# IWatch_MB.net
KiCad netlist of a schematic drawn in Altium Designer
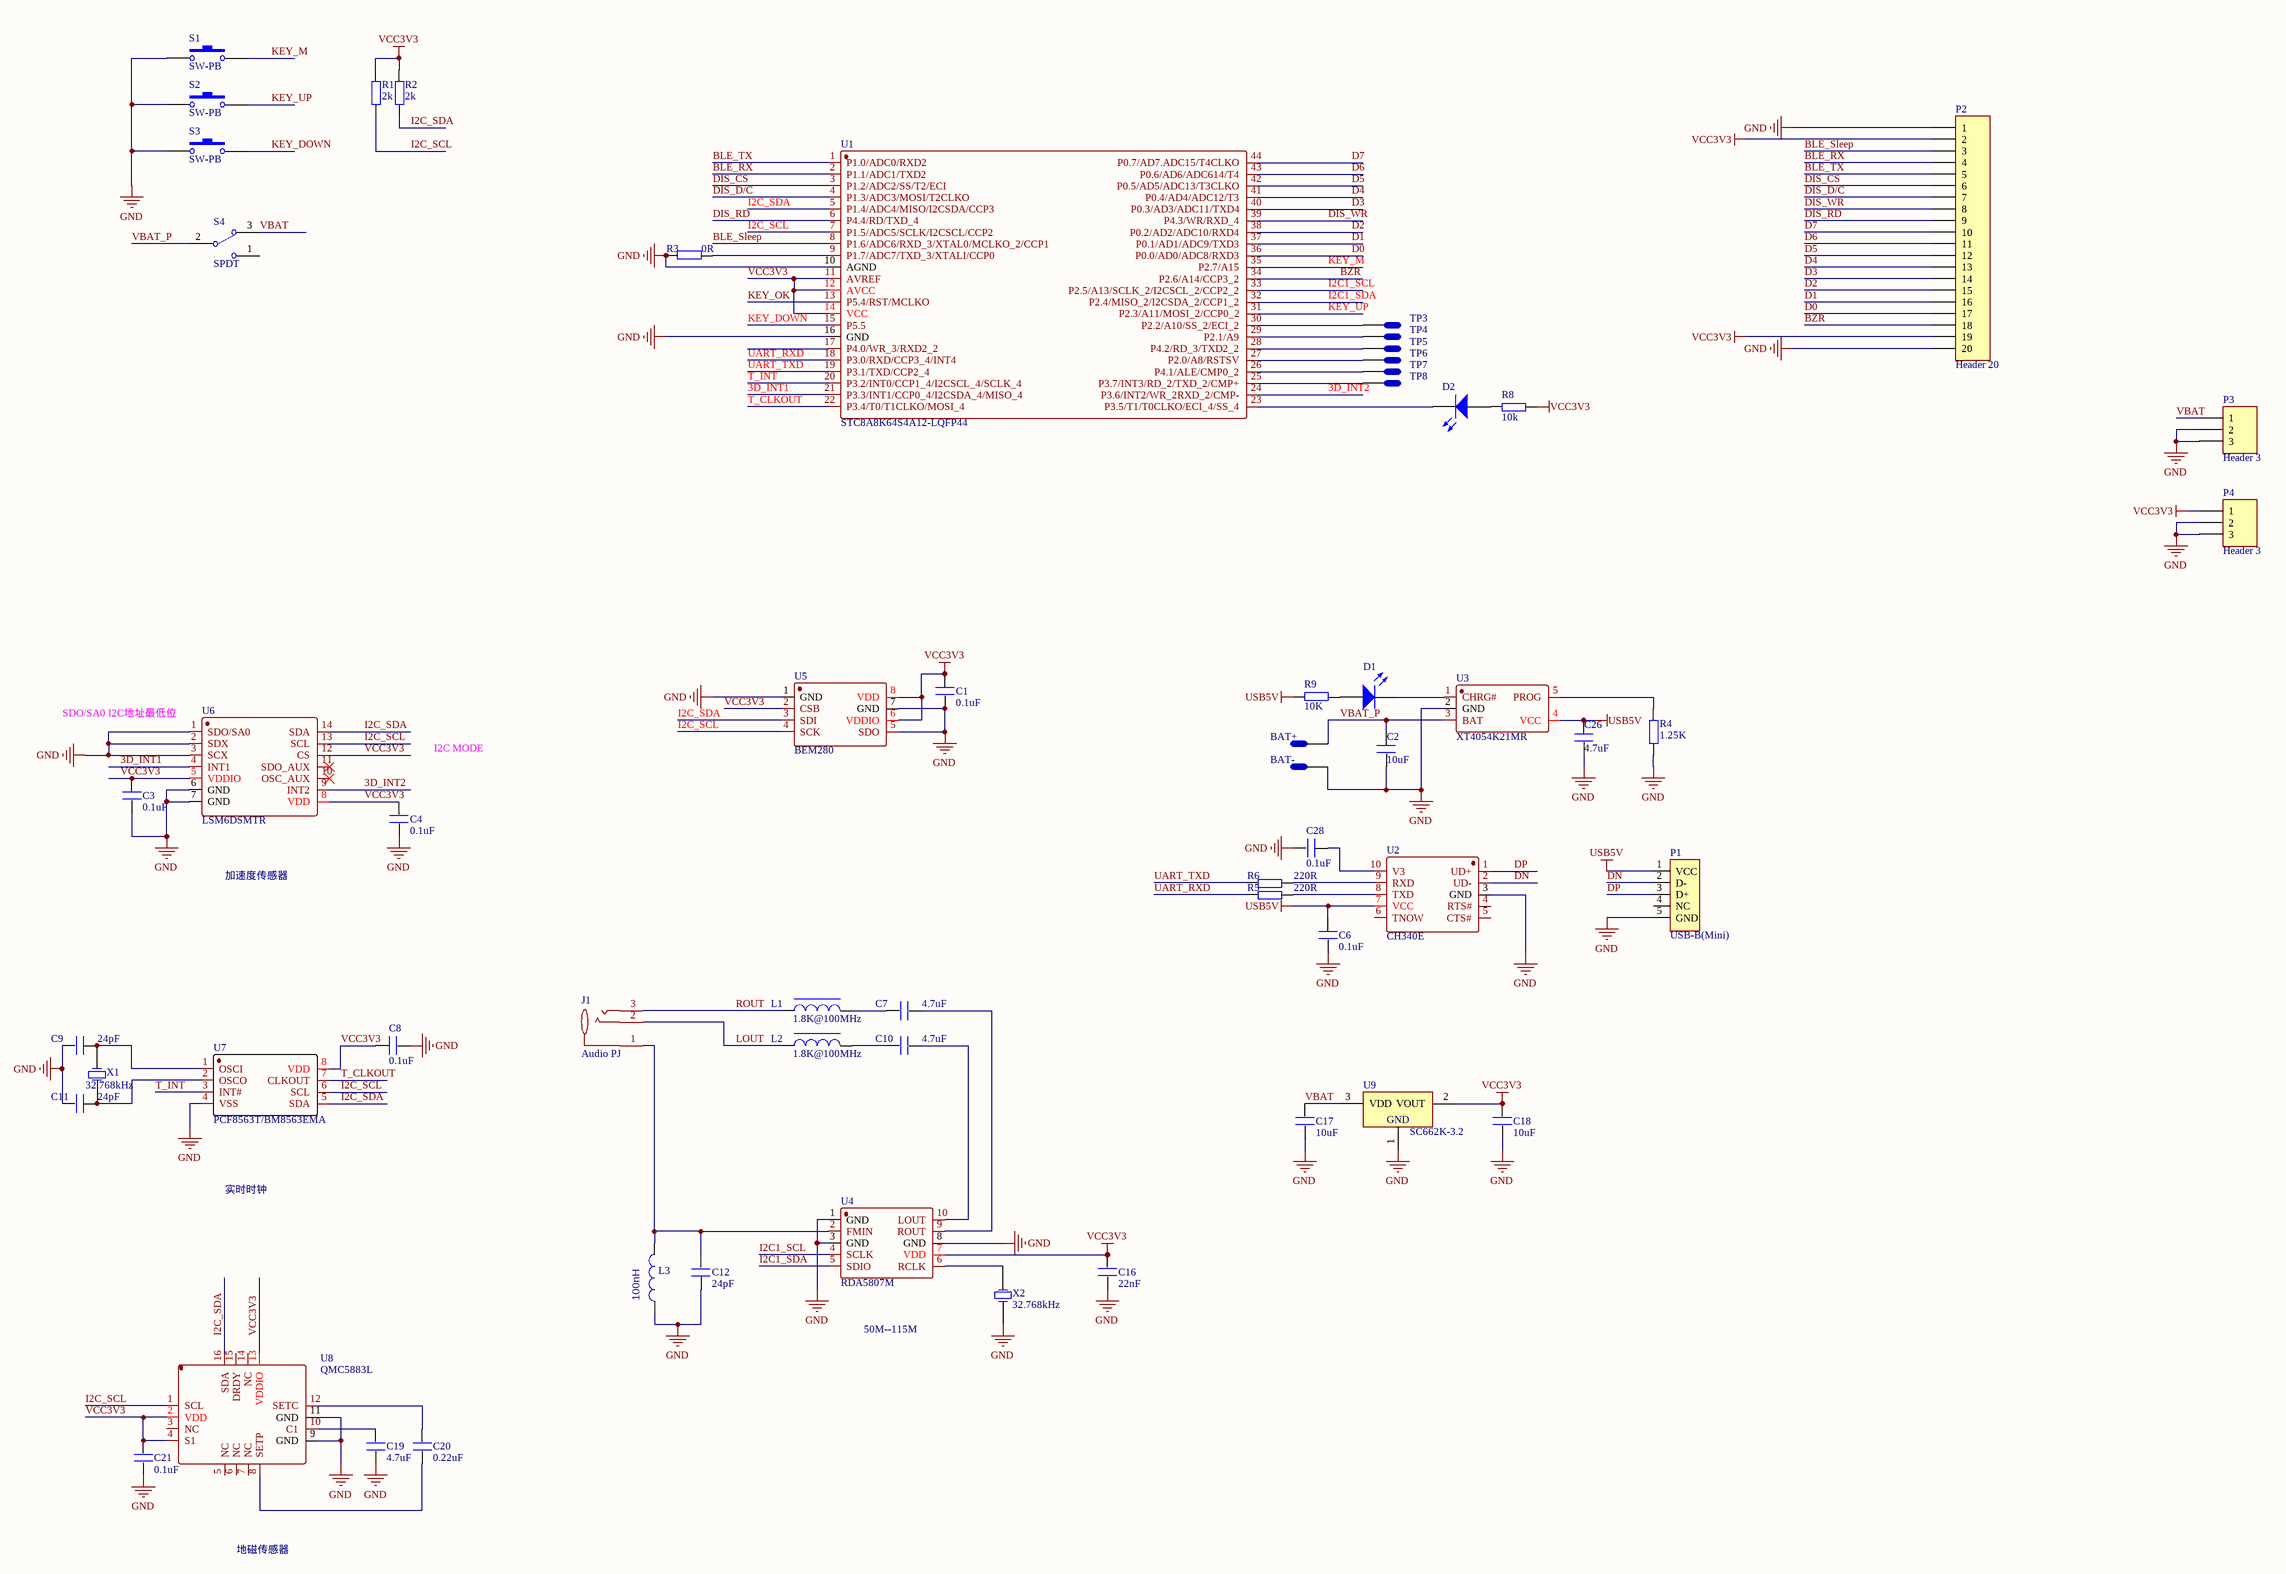
[diagram p0: IWatch_MB.SchDoc]

(export (version "E")
  (design (tool "Eeschema 10.0.6"))
  (components
    (comp (ref "BAT+")
      (value "TP")
      (footprint "TP_1mm")
      (description "TEST POINT")
      (libsource (lib "ADDI9033") (part "TP"))
    )
    (comp (ref "BAT-")
      (value "TP")
      (footprint "TP_1mm")
      (description "TEST POINT")
      (libsource (lib "ADDI9033") (part "TP"))
    )
    (comp (ref "C1")
      (value "0.1uF")
      (footprint "C0603")
      (libsource (lib "Explorer STM32F407封装库2") (part "C"))
    )
    (comp (ref "C2") (value "10uF") (footprint "C0603") (libsource (lib "Explorer STM32F407封装库2") (part "C")))
    (comp (ref "C3")
      (value "0.1uF")
      (footprint "C0603")
      (libsource (lib "Explorer STM32F407封装库2") (part "C"))
    )
    (comp (ref "C4")
      (value "0.1uF")
      (footprint "C0603")
      (libsource (lib "Explorer STM32F407封装库2") (part "C"))
    )
    (comp (ref "C6")
      (value "0.1uF")
      (footprint "C0603")
      (libsource (lib "Explorer STM32F407封装库2") (part "C"))
    )
    (comp (ref "C7")
      (value "4.7uF")
      (footprint "C0603")
      (libsource (lib "Explorer STM32F407封装库2") (part "C"))
    )
    (comp (ref "C8")
      (value "0.1uF")
      (footprint "C0603")
      (libsource (lib "Explorer STM32F407封装库2") (part "C"))
    )
    (comp (ref "C9") (value "24pF") (footprint "C0603") (libsource (lib "Explorer STM32F407封装库2") (part "C")))
    (comp (ref "C10")
      (value "4.7uF")
      (footprint "C0603")
      (libsource (lib "Explorer STM32F407封装库2") (part "C"))
    )
    (comp (ref "C11")
      (value "24pF")
      (footprint "C0603")
      (libsource (lib "Explorer STM32F407封装库2") (part "C"))
    )
    (comp (ref "C12")
      (value "24pF")
      (footprint "C0603")
      (libsource (lib "Explorer STM32F407封装库2") (part "C"))
    )
    (comp (ref "C16")
      (value "22nF")
      (footprint "C0603")
      (libsource (lib "Explorer STM32F407封装库2") (part "C"))
    )
    (comp (ref "C17")
      (value "10uF")
      (footprint "C0603")
      (libsource (lib "Explorer STM32F407封装库2") (part "C"))
    )
    (comp (ref "C18")
      (value "10uF")
      (footprint "C0603")
      (libsource (lib "Explorer STM32F407封装库2") (part "C"))
    )
    (comp (ref "C19")
      (value "4.7uF")
      (footprint "C0603")
      (libsource (lib "Explorer STM32F407封装库2") (part "C"))
    )
    (comp (ref "C20")
      (value "0.22uF")
      (footprint "C0603")
      (libsource (lib "Explorer STM32F407封装库2") (part "C"))
    )
    (comp (ref "C21")
      (value "0.1uF")
      (footprint "C0603")
      (libsource (lib "Explorer STM32F407封装库2") (part "C"))
    )
    (comp (ref "C26")
      (value "4.7uF")
      (footprint "C0603")
      (libsource (lib "Explorer STM32F407封装库2") (part "C"))
    )
    (comp (ref "C28")
      (value "0.1uF")
      (footprint "C0603")
      (libsource (lib "Explorer STM32F407封装库2") (part "C"))
    )
    (comp (ref "D1")
      (value "LED0")
      (footprint "LED_0603")
      (description "Typical INFRARED GaAs LED")
      (fields (field (name "PUBLISHER") "Altium Limited"))
      (libsource (lib "Miscellaneous Devices") (part "LED0"))
    )
    (comp (ref "D2")
      (value "LED0")
      (footprint "LED_0603")
      (description "Typical INFRARED GaAs LED")
      (fields (field (name "PUBLISHER") "Altium Limited"))
      (libsource (lib "Miscellaneous Devices") (part "LED0"))
    )
    (comp (ref "J1") (value "Audio PJ") (footprint "Audio PJ") (libsource (lib "TOF_SCH") (part "Audio PJ")))
    (comp (ref "L1")
      (value "1.8K@100MHz")
      (footprint "R0603")
      (description "铁心电感")
      (libsource (lib "TOF_SCH") (part "INDUCTOR_2"))
    )
    (comp (ref "L2")
      (value "1.8K@100MHz")
      (footprint "R0603")
      (description "铁心电感")
      (libsource (lib "TOF_SCH") (part "INDUCTOR_2"))
    )
    (comp (ref "L3")
      (value "100nH")
      (footprint "R0603")
      (description "Inductor")
      (libsource (lib "TOF_SCH") (part "INDUCTOR"))
    )
    (comp (ref "P1")
      (value "USB-B(Mini)")
      (footprint "MICRO_USB5P_带牛角")
      (libsource (lib "阿波罗STM32F4&F7底板封装库") (part "USB5"))
    )
    (comp (ref "P2")
      (value "Header 20")
      (footprint "HDR_1X20P_1.27MM")
      (description "Header, 20-Pin")
      (fields (field (name "PUBLISHER") "Altium Limited"))
      (libsource (lib "Miscellaneous Connectors") (part "Header 20"))
    )
    (comp (ref "P3")
      (value "Header 3")
      (footprint "HDR_1X3P_1.27MM")
      (description "Header, 3-Pin")
      (fields (field (name "PUBLISHER") "Altium Limited"))
      (libsource (lib "Miscellaneous Connectors") (part "Header 3"))
    )
    (comp (ref "P4")
      (value "Header 3")
      (footprint "HDR_1X3P_1.27MM")
      (description "Header, 3-Pin")
      (fields (field (name "PUBLISHER") "Altium Limited"))
      (libsource (lib "Miscellaneous Connectors") (part "Header 3"))
    )
    (comp (ref "R1") (value "2k") (footprint "R0603") (libsource (lib "Explorer STM32F407封装库2") (part "R")))
    (comp (ref "R2") (value "2k") (footprint "R0603") (libsource (lib "Explorer STM32F407封装库2") (part "R")))
    (comp (ref "R3") (value "0R") (footprint "R0603") (libsource (lib "Explorer STM32F407封装库2") (part "R")))
    (comp (ref "R4")
      (value "1.25K")
      (footprint "R0603")
      (libsource (lib "Explorer STM32F407封装库2") (part "R"))
    )
    (comp (ref "R5") (value "220R") (footprint "R0603") (libsource (lib "Explorer STM32F407封装库2") (part "R")))
    (comp (ref "R6") (value "220R") (footprint "R0603") (libsource (lib "Explorer STM32F407封装库2") (part "R")))
    (comp (ref "R8") (value "10k") (footprint "R0603") (libsource (lib "Explorer STM32F407封装库2") (part "R")))
    (comp (ref "R9") (value "10K") (footprint "R0603") (libsource (lib "Explorer STM32F407封装库2") (part "R")))
    (comp (ref "S1")
      (value "SW-PB")
      (footprint "Button_3x6x3.5mm")
      (description "Switch")
      (fields (field (name "PUBLISHER") "Altium Limited"))
      (libsource (lib "Miscellaneous Devices") (part "SW-PB"))
    )
    (comp (ref "S2")
      (value "SW-PB")
      (footprint "Button_3x6x3.5mm")
      (description "Switch")
      (fields (field (name "PUBLISHER") "Altium Limited"))
      (libsource (lib "Miscellaneous Devices") (part "SW-PB"))
    )
    (comp (ref "S3")
      (value "SW-PB")
      (footprint "Button_3x6x3.5mm")
      (description "Switch")
      (fields (field (name "PUBLISHER") "Altium Limited"))
      (libsource (lib "Miscellaneous Devices") (part "SW-PB"))
    )
    (comp (ref "S4")
      (value "SPDT")
      (footprint "SW-SK12D07_三脚两档")
      (description "Single-Pole Double-Throw")
      (libsource (lib "TOF_SCH") (part "SPDT"))
    )
    (comp (ref "TP3")
      (value "TP")
      (footprint "TP_1mm")
      (description "TEST POINT")
      (libsource (lib "ADDI9033") (part "TP"))
    )
    (comp (ref "TP4")
      (value "TP")
      (footprint "TP_1mm")
      (description "TEST POINT")
      (libsource (lib "ADDI9033") (part "TP"))
    )
    (comp (ref "TP5")
      (value "TP")
      (footprint "TP_1mm")
      (description "TEST POINT")
      (libsource (lib "ADDI9033") (part "TP"))
    )
    (comp (ref "TP6")
      (value "TP")
      (footprint "TP_1mm")
      (description "TEST POINT")
      (libsource (lib "ADDI9033") (part "TP"))
    )
    (comp (ref "TP7")
      (value "TP")
      (footprint "TP_1mm")
      (description "TEST POINT")
      (libsource (lib "ADDI9033") (part "TP"))
    )
    (comp (ref "TP8")
      (value "TP")
      (footprint "TP_1mm")
      (description "TEST POINT")
      (libsource (lib "ADDI9033") (part "TP"))
    )
    (comp (ref "U1")
      (value "STC8A8K64S4A12-LQFP44")
      (libsource (lib "TOF_SCH") (part "STC8A8K64S4A12-LQFP44"))
    )
    (comp (ref "U2") (value "CH340E") (footprint "MSOP-10") (libsource (lib "IWatch") (part "CH340E")))
    (comp (ref "U3")
      (value "XT4054K21MR")
      (footprint "SOT23-5")
      (libsource (lib "TOF_SCH") (part "XT4054K21MR"))
    )
    (comp (ref "U4")
      (value "RDA5807M")
      (footprint "MSOP-10")
      (description "SINGLE-CHIP BROADCAST FM RADIO TUNER")
      (libsource (lib "TOF_SCH") (part "RDA5807M"))
    )
    (comp (ref "U5")
      (value "BEM280")
      (footprint "LGA-8")
      (description "Integrated Environmental Unit")
      (libsource (lib "IWatch") (part "BEM280"))
    )
    (comp (ref "U6")
      (value "LSM6DSMTR")
      (footprint "LGA-14L")
      (description "3D accelerometer and 3D gyroscope")
      (libsource (lib "TOF_SCH") (part "LSM6DSMTR"))
    )
    (comp (ref "U7")
      (value "PCF8563T/BM8563EMA")
      (footprint "MSOP8")
      (description "Real-time clock/calendar")
      (libsource (lib "TOF_SCH") (part "PCF8563"))
    )
    (comp (ref "U8")
      (value "QMC5883L")
      (footprint "LGA-16")
      (description "3-Axis Magnetic Sensor")
      (libsource (lib "TOF_SCH") (part "QMC5883L"))
    )
    (comp (ref "U9")
      (value "SC662K-3.2")
      (footprint "SOT23-3")
      (description "Low Dropout,  250mA")
      (libsource (lib "TOF_SCH") (part "SC662K-3.2"))
    )
    (comp (ref "X1")
      (value "32.768kHz")
      (footprint "XTAL_2012_2P")
      (libsource (lib "TOF_SCH") (part "XTAL_2"))
    )
    (comp (ref "X2")
      (value "32.768kHz")
      (footprint "XTAL_2012_2P")
      (libsource (lib "TOF_SCH") (part "XTAL_2"))
    )
  )
  (nets
    (net (code "1") (name "/3D_INT1") (class "Default")
      (node (ref "U1") (pin "21") (pinfunction "P3.3/INT1/CCP0_4/I2CSDA_4/MISO_4_21") (pintype "passive"))
      (node (ref "U6") (pin "4") (pinfunction "INT1_4") (pintype "passive"))
    )
    (net (code "2") (name "/3D_INT2") (class "Default")
      (node (ref "U1") (pin "24") (pinfunction "P3.6/INT2/WR_2RXD_2/CMP-_24") (pintype "passive"))
      (node (ref "U6") (pin "9") (pinfunction "INT2_9") (pintype "passive"))
    )
    (net (code "3") (name "/BLE_RX") (class "Default")
      (node (ref "P2") (pin "4") (pinfunction "4_4") (pintype "passive"))
      (node (ref "U1") (pin "2") (pinfunction "P1.1/ADC1/TXD2_2") (pintype "passive"))
    )
    (net (code "4") (name "/BLE_Sleep") (class "Default")
      (node (ref "P2") (pin "3") (pinfunction "3_3") (pintype "passive"))
      (node (ref "U1") (pin "8") (pinfunction "P1.6/ADC6/RXD_3/XTAL0/MCLKO_2/CCP1_8") (pintype "passive"))
    )
    (net (code "5") (name "/BLE_TX") (class "Default")
      (node (ref "P2") (pin "5") (pinfunction "5_5") (pintype "passive"))
      (node (ref "U1") (pin "1") (pinfunction "P1.0/ADC0/RXD2_1") (pintype "passive"))
    )
    (net (code "6") (name "/BZR") (class "Default")
      (node (ref "P2") (pin "18") (pinfunction "18_18") (pintype "passive"))
      (node (ref "U1") (pin "34") (pinfunction "P2.6/A14/CCP3_2_34") (pintype "passive"))
    )
    (net (code "7") (name "/D0") (class "Default")
      (node (ref "P2") (pin "17") (pinfunction "17_17") (pintype "passive"))
      (node (ref "U1") (pin "36") (pinfunction "P0.0/AD0/ADC8/RXD3_36") (pintype "passive"))
    )
    (net (code "8") (name "/D1") (class "Default")
      (node (ref "P2") (pin "16") (pinfunction "16_16") (pintype "passive"))
      (node (ref "U1") (pin "37") (pinfunction "P0.1/AD1/ADC9/TXD3_37") (pintype "passive"))
    )
    (net (code "9") (name "/D2") (class "Default")
      (node (ref "P2") (pin "15") (pinfunction "15_15") (pintype "passive"))
      (node (ref "U1") (pin "38") (pinfunction "P0.2/AD2/ADC10/RXD4_38") (pintype "passive"))
    )
    (net (code "10") (name "/D3") (class "Default")
      (node (ref "P2") (pin "14") (pinfunction "14_14") (pintype "passive"))
      (node (ref "U1") (pin "40") (pinfunction "P0.3/AD3/ADC11/TXD4_40") (pintype "passive"))
    )
    (net (code "11") (name "/D4") (class "Default")
      (node (ref "P2") (pin "13") (pinfunction "13_13") (pintype "passive"))
      (node (ref "U1") (pin "41") (pinfunction "P0.4/AD4/ADC12/T3_41") (pintype "passive"))
    )
    (net (code "12") (name "/D5") (class "Default")
      (node (ref "P2") (pin "12") (pinfunction "12_12") (pintype "passive"))
      (node (ref "U1") (pin "42") (pinfunction "P0.5/AD5/ADC13/T3CLKO_42") (pintype "passive"))
    )
    (net (code "13") (name "/D6") (class "Default")
      (node (ref "P2") (pin "11") (pinfunction "11_11") (pintype "passive"))
      (node (ref "U1") (pin "43") (pinfunction "P0.6/AD6/ADC614/T4_43") (pintype "passive"))
    )
    (net (code "14") (name "/D7") (class "Default")
      (node (ref "P2") (pin "10") (pinfunction "10_10") (pintype "passive"))
      (node (ref "U1") (pin "44") (pinfunction "P0.7/AD7.ADC15/T4CLKO_44") (pintype "passive"))
    )
    (net (code "15") (name "/DIS_CS") (class "Default")
      (node (ref "P2") (pin "6") (pinfunction "6_6") (pintype "passive"))
      (node (ref "U1") (pin "3") (pinfunction "P1.2/ADC2/SS/T2/ECI_3") (pintype "passive"))
    )
    (net (code "16") (name "/DIS_D{slash}C") (class "Default")
      (node (ref "P2") (pin "7") (pinfunction "7_7") (pintype "passive"))
      (node (ref "U1") (pin "4") (pinfunction "P1.3/ADC3/MOSI/T2CLKO_4") (pintype "passive"))
    )
    (net (code "17") (name "/DIS_RD") (class "Default")
      (node (ref "P2") (pin "9") (pinfunction "9_9") (pintype "passive"))
      (node (ref "U1") (pin "6") (pinfunction "P4.4/RD/TXD_4_6") (pintype "passive"))
    )
    (net (code "18") (name "/DIS_WR") (class "Default")
      (node (ref "P2") (pin "8") (pinfunction "8_8") (pintype "passive"))
      (node (ref "U1") (pin "39") (pinfunction "P4.3/WR/RXD_4_39") (pintype "passive"))
    )
    (net (code "19") (name "/DN") (class "Default")
      (node (ref "P1") (pin "2") (pinfunction "D-_2") (pintype "passive"))
      (node (ref "U2") (pin "2") (pinfunction "UD-_2") (pintype "passive"))
    )
    (net (code "20") (name "/DP") (class "Default")
      (node (ref "P1") (pin "3") (pinfunction "D+_3") (pintype "passive"))
      (node (ref "U2") (pin "1") (pinfunction "UD+_1") (pintype "passive"))
    )
    (net (code "21") (name "/I2C1_SCL") (class "Default")
      (node (ref "U1") (pin "33") (pinfunction "P2.5/A13/SCLK_2/I2CSCL_2/CCP2_2_33") (pintype "passive"))
      (node (ref "U4") (pin "4") (pinfunction "SCLK_4") (pintype "passive"))
    )
    (net (code "22") (name "/I2C1_SDA") (class "Default")
      (node (ref "U1") (pin "32") (pinfunction "P2.4/MISO_2/I2CSDA_2/CCP1_2_32") (pintype "passive"))
      (node (ref "U4") (pin "5") (pinfunction "SDIO_5") (pintype "passive"))
    )
    (net (code "23") (name "/I2C_SCL") (class "Default")
      (node (ref "R1") (pin "1") (pintype "passive"))
      (node (ref "U1") (pin "7") (pinfunction "P1.5/ADC5/SCLK/I2CSCL/CCP2_7") (pintype "passive"))
      (node (ref "U5") (pin "4") (pinfunction "SCK_4") (pintype "passive"))
      (node (ref "U6") (pin "13") (pinfunction "SCL_13") (pintype "passive"))
      (node (ref "U7") (pin "6") (pinfunction "SCL_6") (pintype "passive"))
      (node (ref "U8") (pin "1") (pinfunction "SCL_1") (pintype "passive"))
    )
    (net (code "24") (name "/I2C_SDA") (class "Default")
      (node (ref "R2") (pin "1") (pintype "passive"))
      (node (ref "U1") (pin "5") (pinfunction "P1.4/ADC4/MISO/I2CSDA/CCP3_5") (pintype "passive"))
      (node (ref "U5") (pin "3") (pinfunction "SDI_3") (pintype "passive"))
      (node (ref "U6") (pin "14") (pinfunction "SDA_14") (pintype "passive"))
      (node (ref "U7") (pin "5") (pinfunction "SDA_5") (pintype "passive"))
      (node (ref "U8") (pin "16") (pinfunction "SDA_16") (pintype "passive"))
    )
    (net (code "25") (name "/KEY_DOWN") (class "Default")
      (node (ref "S3") (pin "2") (pinfunction "2_2") (pintype "passive"))
      (node (ref "U1") (pin "15") (pinfunction "P5.5_15") (pintype "passive"))
    )
    (net (code "26") (name "/KEY_M") (class "Default")
      (node (ref "S1") (pin "2") (pinfunction "2_2") (pintype "passive"))
      (node (ref "U1") (pin "35") (pinfunction "P2.7/A15_35") (pintype "passive"))
    )
    (net (code "27") (name "/KEY_OK") (class "Default")
      (node (ref "U1") (pin "13") (pinfunction "P5.4/RST/MCLKO_13") (pintype "passive"))
    )
    (net (code "28") (name "/KEY_UP") (class "Default")
      (node (ref "S2") (pin "2") (pinfunction "2_2") (pintype "passive"))
      (node (ref "U1") (pin "31") (pinfunction "P2.3/A11/MOSI_2/CCP0_2_31") (pintype "passive"))
    )
    (net (code "29") (name "/LOUT") (class "Default")
      (node (ref "J1") (pin "2") (pinfunction "2_2") (pintype "passive"))
      (node (ref "L2") (pin "1") (pinfunction "1_1") (pintype "passive"))
    )
    (net (code "30") (name "/ROUT") (class "Default")
      (node (ref "J1") (pin "3") (pinfunction "3_3") (pintype "passive"))
      (node (ref "L1") (pin "1") (pinfunction "1_1") (pintype "passive"))
    )
    (net (code "31") (name "/T_CLKOUT") (class "Default")
      (node (ref "U1") (pin "22") (pinfunction "P3.4/T0/T1CLKO/MOSI_4_22") (pintype "passive"))
      (node (ref "U7") (pin "7") (pinfunction "CLKOUT_7") (pintype "passive"))
    )
    (net (code "32") (name "/T_INT") (class "Default")
      (node (ref "U1") (pin "20") (pinfunction "P3.2/INT0/CCP1_4/I2CSCL_4/SCLK_4_20") (pintype "passive"))
      (node (ref "U7") (pin "3") (pinfunction "INT#_3") (pintype "passive"))
    )
    (net (code "33") (name "/UART_RXD") (class "Default")
      (node (ref "R5") (pin "1") (pintype "passive"))
      (node (ref "U1") (pin "18") (pinfunction "P3.0/RXD/CCP3_4/INT4_18") (pintype "passive"))
    )
    (net (code "34") (name "/UART_TXD") (class "Default")
      (node (ref "R6") (pin "1") (pintype "passive"))
      (node (ref "U1") (pin "19") (pinfunction "P3.1/TXD/CCP2_4_19") (pintype "passive"))
    )
    (net (code "35") (name "/VBAT") (class "Default")
      (node (ref "C17") (pin "2") (pintype "passive"))
      (node (ref "P3") (pin "1") (pinfunction "1_1") (pintype "passive"))
      (node (ref "S4") (pin "3") (pinfunction "3_3") (pintype "passive"))
      (node (ref "U9") (pin "3") (pinfunction "VDD_3") (pintype "passive"))
    )
    (net (code "36") (name "/VBAT_P") (class "Default")
      (node (ref "BAT+") (pin "1") (pinfunction "TP?_1") (pintype "passive"))
      (node (ref "C2") (pin "2") (pintype "passive"))
      (node (ref "S4") (pin "2") (pinfunction "2_2") (pintype "passive"))
      (node (ref "U3") (pin "3") (pinfunction "BAT_3") (pintype "passive"))
    )
    (net (code "37") (name "GND") (class "Default")
      (node (ref "BAT-") (pin "1") (pinfunction "TP?_1") (pintype "passive"))
      (node (ref "C1") (pin "1") (pintype "passive"))
      (node (ref "C11") (pin "2") (pintype "passive"))
      (node (ref "C12") (pin "2") (pintype "passive"))
      (node (ref "C16") (pin "1") (pintype "passive"))
      (node (ref "C17") (pin "1") (pintype "passive"))
      (node (ref "C18") (pin "1") (pintype "passive"))
      (node (ref "C19") (pin "2") (pintype "passive"))
      (node (ref "C2") (pin "1") (pintype "passive"))
      (node (ref "C21") (pin "1") (pintype "passive"))
      (node (ref "C26") (pin "1") (pintype "passive"))
      (node (ref "C28") (pin "2") (pintype "passive"))
      (node (ref "C3") (pin "1") (pintype "passive"))
      (node (ref "C4") (pin "1") (pintype "passive"))
      (node (ref "C6") (pin "1") (pintype "passive"))
      (node (ref "C8") (pin "2") (pintype "passive"))
      (node (ref "C9") (pin "2") (pintype "passive"))
      (node (ref "L3") (pin "1") (pinfunction "1_1") (pintype "passive"))
      (node (ref "P1") (pin "5") (pinfunction "GND_5") (pintype "passive"))
      (node (ref "P2") (pin "1") (pinfunction "1_1") (pintype "passive"))
      (node (ref "P2") (pin "20") (pinfunction "20_20") (pintype "passive"))
      (node (ref "P3") (pin "2") (pinfunction "2_2") (pintype "passive"))
      (node (ref "P3") (pin "3") (pinfunction "3_3") (pintype "passive"))
      (node (ref "P4") (pin "2") (pinfunction "2_2") (pintype "passive"))
      (node (ref "P4") (pin "3") (pinfunction "3_3") (pintype "passive"))
      (node (ref "R3") (pin "2") (pintype "passive"))
      (node (ref "R4") (pin "1") (pintype "passive"))
      (node (ref "S1") (pin "1") (pinfunction "1_1") (pintype "passive"))
      (node (ref "S2") (pin "1") (pinfunction "1_1") (pintype "passive"))
      (node (ref "S3") (pin "1") (pinfunction "1_1") (pintype "passive"))
      (node (ref "U1") (pin "10") (pinfunction "AGND_10") (pintype "passive"))
      (node (ref "U1") (pin "16") (pinfunction "GND_16") (pintype "passive"))
      (node (ref "U2") (pin "3") (pinfunction "GND_3") (pintype "passive"))
      (node (ref "U3") (pin "2") (pinfunction "GND_2") (pintype "passive"))
      (node (ref "U4") (pin "1") (pinfunction "GND_1") (pintype "passive"))
      (node (ref "U4") (pin "3") (pinfunction "GND_3") (pintype "passive"))
      (node (ref "U4") (pin "8") (pinfunction "GND_8") (pintype "passive"))
      (node (ref "U5") (pin "1") (pinfunction "GND_1") (pintype "passive"))
      (node (ref "U5") (pin "5") (pinfunction "SDO_5") (pintype "passive"))
      (node (ref "U5") (pin "7") (pinfunction "GND_7") (pintype "passive"))
      (node (ref "U6") (pin "1") (pinfunction "SDO/SA0_1") (pintype "passive"))
      (node (ref "U6") (pin "2") (pinfunction "SDX_2") (pintype "passive"))
      (node (ref "U6") (pin "3") (pinfunction "SCX_3") (pintype "passive"))
      (node (ref "U6") (pin "6") (pinfunction "GND_6") (pintype "passive"))
      (node (ref "U6") (pin "7") (pinfunction "GND_7") (pintype "passive"))
      (node (ref "U7") (pin "4") (pinfunction "VSS_4") (pintype "passive"))
      (node (ref "U8") (pin "11") (pinfunction "GND_11") (pintype "passive"))
      (node (ref "U8") (pin "9") (pinfunction "GND_9") (pintype "passive"))
      (node (ref "U9") (pin "1") (pinfunction "GND_1") (pintype "passive"))
      (node (ref "X2") (pin "1") (pinfunction "OSC1_1") (pintype "passive"))
    )
    (net (code "38") (name "Net-(C7-Pad2)") (class "Default")
      (node (ref "C7") (pin "2") (pintype "passive"))
      (node (ref "L1") (pin "2") (pinfunction "2_2") (pintype "passive"))
    )
    (net (code "39") (name "Net-(C10-Pad2)") (class "Default")
      (node (ref "C10") (pin "2") (pintype "passive"))
      (node (ref "L2") (pin "2") (pinfunction "2_2") (pintype "passive"))
    )
    (net (code "40") (name "Net-(D1-A)") (class "Default")
      (node (ref "D1") (pin "1") (pinfunction "A_1") (pintype "passive"))
      (node (ref "R9") (pin "1") (pintype "passive"))
    )
    (net (code "41") (name "Net-(D1-K)") (class "Default")
      (node (ref "D1") (pin "2") (pinfunction "K_2") (pintype "passive"))
      (node (ref "U3") (pin "1") (pinfunction "CHRG#_1") (pintype "passive"))
    )
    (net (code "42") (name "Net-(D2-A)") (class "Default")
      (node (ref "D2") (pin "1") (pinfunction "A_1") (pintype "passive"))
      (node (ref "R8") (pin "1") (pintype "passive"))
    )
    (net (code "43") (name "Net-(D2-K)") (class "Default")
      (node (ref "D2") (pin "2") (pinfunction "K_2") (pintype "passive"))
      (node (ref "U1") (pin "23") (pinfunction "P3.5/T1/T0CLKO/ECI_4/SS_4_23") (pintype "passive"))
    )
    (net (code "44") (name "Net-(TP3-TP?)") (class "Default")
      (node (ref "TP3") (pin "1") (pinfunction "TP?_1") (pintype "passive"))
      (node (ref "U1") (pin "30") (pinfunction "P2.2/A10/SS_2/ECI_2_30") (pintype "passive"))
    )
    (net (code "45") (name "Net-(TP4-TP?)") (class "Default")
      (node (ref "TP4") (pin "1") (pinfunction "TP?_1") (pintype "passive"))
      (node (ref "U1") (pin "29") (pinfunction "P2.1/A9_29") (pintype "passive"))
    )
    (net (code "46") (name "Net-(TP5-TP?)") (class "Default")
      (node (ref "TP5") (pin "1") (pinfunction "TP?_1") (pintype "passive"))
      (node (ref "U1") (pin "28") (pinfunction "P4.2/RD_3/TXD2_2_28") (pintype "passive"))
    )
    (net (code "47") (name "Net-(TP6-TP?)") (class "Default")
      (node (ref "TP6") (pin "1") (pinfunction "TP?_1") (pintype "passive"))
      (node (ref "U1") (pin "27") (pinfunction "P2.0/A8/RSTSV_27") (pintype "passive"))
    )
    (net (code "48") (name "Net-(TP7-TP?)") (class "Default")
      (node (ref "TP7") (pin "1") (pinfunction "TP?_1") (pintype "passive"))
      (node (ref "U1") (pin "26") (pinfunction "P4.1/ALE/CMP0_2_26") (pintype "passive"))
    )
    (net (code "49") (name "Net-(TP8-TP?)") (class "Default")
      (node (ref "TP8") (pin "1") (pinfunction "TP?_1") (pintype "passive"))
      (node (ref "U1") (pin "25") (pinfunction "P3.7/INT3/RD_2/TXD_2/CMP+_25") (pintype "passive"))
    )
    (net (code "50") (name "Net-(U1-P1.7{slash}ADC7{slash}TXD_3{slash}XTALI{slash}CCP0)") (class "Default")
      (node (ref "R3") (pin "1") (pintype "passive"))
      (node (ref "U1") (pin "9") (pinfunction "P1.7/ADC7/TXD_3/XTALI/CCP0_9") (pintype "passive"))
    )
    (net (code "51") (name "Net-(U2-RXD)") (class "Default")
      (node (ref "R6") (pin "2") (pintype "passive"))
      (node (ref "U2") (pin "9") (pinfunction "RXD_9") (pintype "passive"))
    )
    (net (code "52") (name "Net-(U2-TXD)") (class "Default")
      (node (ref "R5") (pin "2") (pintype "passive"))
      (node (ref "U2") (pin "8") (pinfunction "TXD_8") (pintype "passive"))
    )
    (net (code "53") (name "Net-(U2-V3)") (class "Default")
      (node (ref "C28") (pin "1") (pintype "passive"))
      (node (ref "U2") (pin "10") (pinfunction "V3_10") (pintype "passive"))
    )
    (net (code "54") (name "Net-(U3-PROG)") (class "Default")
      (node (ref "R4") (pin "2") (pintype "passive"))
      (node (ref "U3") (pin "5") (pinfunction "PROG_5") (pintype "passive"))
    )
    (net (code "55") (name "Net-(U4-FMIN)") (class "Default")
      (node (ref "C12") (pin "1") (pintype "passive"))
      (node (ref "J1") (pin "1") (pinfunction "1_1") (pintype "passive"))
      (node (ref "L3") (pin "2") (pinfunction "2_2") (pintype "passive"))
      (node (ref "U4") (pin "2") (pinfunction "FMIN_2") (pintype "passive"))
    )
    (net (code "56") (name "Net-(U4-LOUT)") (class "Default")
      (node (ref "C10") (pin "1") (pintype "passive"))
      (node (ref "U4") (pin "10") (pinfunction "LOUT_10") (pintype "passive"))
    )
    (net (code "57") (name "Net-(U4-RCLK)") (class "Default")
      (node (ref "U4") (pin "6") (pinfunction "RCLK_6") (pintype "passive"))
      (node (ref "X2") (pin "2") (pinfunction "OSC2_2") (pintype "passive"))
    )
    (net (code "58") (name "Net-(U4-ROUT)") (class "Default")
      (node (ref "C7") (pin "1") (pintype "passive"))
      (node (ref "U4") (pin "9") (pinfunction "ROUT_9") (pintype "passive"))
    )
    (net (code "59") (name "Net-(U7-OSCI)") (class "Default")
      (node (ref "C9") (pin "1") (pintype "passive"))
      (node (ref "U7") (pin "1") (pinfunction "OSCI_1") (pintype "passive"))
      (node (ref "X1") (pin "1") (pinfunction "OSC1_1") (pintype "passive"))
    )
    (net (code "60") (name "Net-(U7-OSCO)") (class "Default")
      (node (ref "C11") (pin "1") (pintype "passive"))
      (node (ref "U7") (pin "2") (pinfunction "OSCO_2") (pintype "passive"))
      (node (ref "X1") (pin "2") (pinfunction "OSC2_2") (pintype "passive"))
    )
    (net (code "61") (name "Net-(U8-C1)") (class "Default")
      (node (ref "C19") (pin "1") (pintype "passive"))
      (node (ref "U8") (pin "10") (pinfunction "C1_10") (pintype "passive"))
    )
    (net (code "62") (name "Net-(U8-SETC)") (class "Default")
      (node (ref "C20") (pin "1") (pintype "passive"))
      (node (ref "U8") (pin "12") (pinfunction "SETC_12") (pintype "passive"))
    )
    (net (code "63") (name "Net-(U8-SETP)") (class "Default")
      (node (ref "C20") (pin "2") (pintype "passive"))
      (node (ref "U8") (pin "8") (pinfunction "SETP_8") (pintype "passive"))
    )
    (net (code "64") (name "USB5V") (class "Default")
      (node (ref "C26") (pin "2") (pintype "passive"))
      (node (ref "C6") (pin "2") (pintype "passive"))
      (node (ref "P1") (pin "1") (pinfunction "VCC_1") (pintype "passive"))
      (node (ref "R9") (pin "2") (pintype "passive"))
      (node (ref "U2") (pin "7") (pinfunction "VCC_7") (pintype "passive"))
      (node (ref "U3") (pin "4") (pinfunction "VCC_4") (pintype "passive"))
    )
    (net (code "65") (name "VCC3V3") (class "Default")
      (node (ref "C1") (pin "2") (pintype "passive"))
      (node (ref "C16") (pin "2") (pintype "passive"))
      (node (ref "C18") (pin "2") (pintype "passive"))
      (node (ref "C21") (pin "2") (pintype "passive"))
      (node (ref "C3") (pin "2") (pintype "passive"))
      (node (ref "C4") (pin "2") (pintype "passive"))
      (node (ref "C8") (pin "1") (pintype "passive"))
      (node (ref "P2") (pin "19") (pinfunction "19_19") (pintype "passive"))
      (node (ref "P2") (pin "2") (pinfunction "2_2") (pintype "passive"))
      (node (ref "P4") (pin "1") (pinfunction "1_1") (pintype "passive"))
      (node (ref "R1") (pin "2") (pintype "passive"))
      (node (ref "R2") (pin "2") (pintype "passive"))
      (node (ref "R8") (pin "2") (pintype "passive"))
      (node (ref "U1") (pin "11") (pinfunction "AVREF_11") (pintype "passive"))
      (node (ref "U1") (pin "12") (pinfunction "AVCC_12") (pintype "passive"))
      (node (ref "U1") (pin "14") (pinfunction "VCC_14") (pintype "passive"))
      (node (ref "U4") (pin "7") (pinfunction "VDD_7") (pintype "passive"))
      (node (ref "U5") (pin "2") (pinfunction "CSB_2") (pintype "passive"))
      (node (ref "U5") (pin "6") (pinfunction "VDDIO_6") (pintype "passive"))
      (node (ref "U5") (pin "8") (pinfunction "VDD_8") (pintype "passive"))
      (node (ref "U6") (pin "12") (pinfunction "CS_12") (pintype "passive"))
      (node (ref "U6") (pin "5") (pinfunction "VDDIO_5") (pintype "passive"))
      (node (ref "U6") (pin "8") (pinfunction "VDD_8") (pintype "passive"))
      (node (ref "U7") (pin "8") (pinfunction "VDD_8") (pintype "passive"))
      (node (ref "U8") (pin "13") (pinfunction "VDDIO_13") (pintype "passive"))
      (node (ref "U8") (pin "2") (pinfunction "VDD_2") (pintype "passive"))
      (node (ref "U8") (pin "4") (pinfunction "S1_4") (pintype "passive"))
      (node (ref "U9") (pin "2") (pinfunction "VOUT_2") (pintype "passive"))
    )
    (net (code "66") (name "unconnected-(P1-NC-Pad4)") (class "Default")
      (node (ref "P1") (pin "4") (pinfunction "NC_4") (pintype "passive"))
    )
    (net (code "67") (name "unconnected-(S4-Pad1)") (class "Default")
      (node (ref "S4") (pin "1") (pinfunction "1_1") (pintype "passive"))
    )
    (net (code "68") (name "unconnected-(U1-P4.0{slash}WR_3{slash}RXD2_2-Pad17)") (class "Default")
      (node (ref "U1") (pin "17") (pinfunction "P4.0/WR_3/RXD2_2_17") (pintype "passive"))
    )
    (net (code "69") (name "unconnected-(U2-CTS#-Pad5)") (class "Default")
      (node (ref "U2") (pin "5") (pinfunction "CTS#_5") (pintype "passive"))
    )
    (net (code "70") (name "unconnected-(U2-RTS#-Pad4)") (class "Default")
      (node (ref "U2") (pin "4") (pinfunction "RTS#_4") (pintype "passive"))
    )
    (net (code "71") (name "unconnected-(U2-TNOW-Pad6)") (class "Default")
      (node (ref "U2") (pin "6") (pinfunction "TNOW_6") (pintype "passive"))
    )
    (net (code "72") (name "unconnected-(U6-OSC_AUX-Pad10)") (class "Default")
      (node (ref "U6") (pin "10") (pinfunction "OSC_AUX_10") (pintype "passive+no_connect"))
    )
    (net (code "73") (name "unconnected-(U6-SDO_AUX-Pad11)") (class "Default")
      (node (ref "U6") (pin "11") (pinfunction "SDO_AUX_11") (pintype "passive+no_connect"))
    )
    (net (code "74") (name "unconnected-(U8-DRDY-Pad15)") (class "Default")
      (node (ref "U8") (pin "15") (pinfunction "DRDY_15") (pintype "passive"))
    )
    (net (code "75") (name "unconnected-(U8-NC-Pad3)") (class "Default")
      (node (ref "U8") (pin "3") (pinfunction "NC_3") (pintype "passive"))
    )
    (net (code "76") (name "unconnected-(U8-NC-Pad5)") (class "Default")
      (node (ref "U8") (pin "5") (pinfunction "NC_5") (pintype "passive"))
    )
    (net (code "77") (name "unconnected-(U8-NC-Pad6)") (class "Default")
      (node (ref "U8") (pin "6") (pinfunction "NC_6") (pintype "passive"))
    )
    (net (code "78") (name "unconnected-(U8-NC-Pad7)") (class "Default")
      (node (ref "U8") (pin "7") (pinfunction "NC_7") (pintype "passive"))
    )
    (net (code "79") (name "unconnected-(U8-NC-Pad14)") (class "Default")
      (node (ref "U8") (pin "14") (pinfunction "NC_14") (pintype "passive"))
    )
  )
)
